# RollerShutterNode_EN.net
KiCad netlist of a schematic drawn in EAGLE
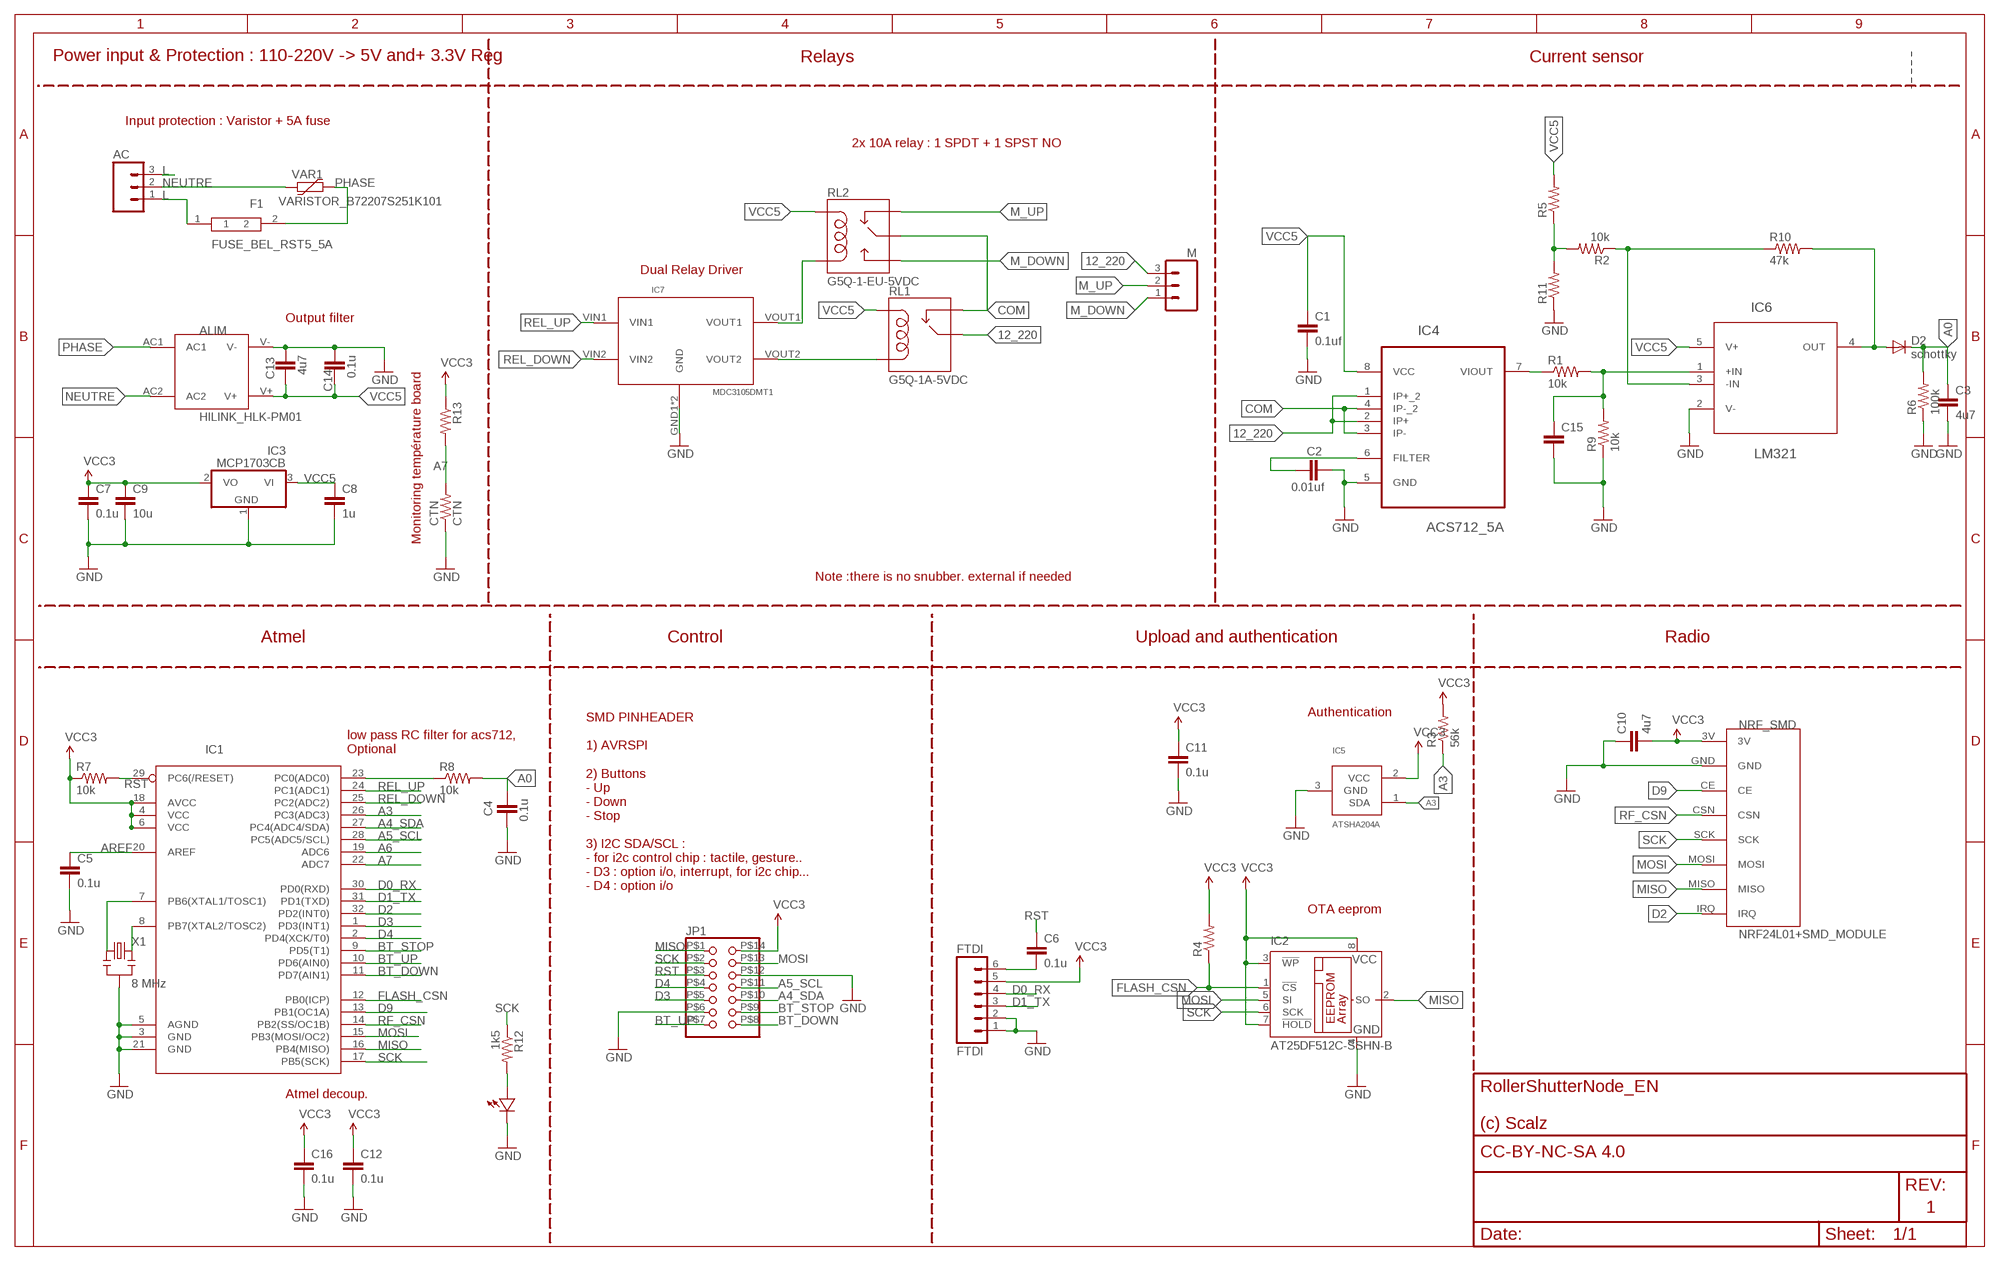
[diagram p0: schematic, sheet 1]

(export (version "E")
  (design (tool "Eeschema 10.0.6"))
  (components
    (comp (ref "AC")
      (value "M03-SCREW-5MM")
      (footprint "eagle-import:SCREWTERMINAL-5MM-3")
      (libsource (lib "eagle-import") (part "M03-SCREW-5MM"))
    )
    (comp (ref "ALIM")
      (value "HILINK_HLK-PM01")
      (footprint "eagle-import:HILINK_HLK-PM01")
      (libsource (lib "eagle-import") (part "HILINK_HLK-PM01"))
    )
    (comp (ref "C1")
      (value "0.1uf")
      (footprint "eagle-import:0805-CAP")
      (libsource (lib "eagle-import") (part "CAP0805-CAP"))
    )
    (comp (ref "C2")
      (value "0.01uf")
      (footprint "eagle-import:0805-CAP")
      (libsource (lib "eagle-import") (part "CAP0805-CAP"))
    )
    (comp (ref "C3")
      (value "4u7")
      (footprint "eagle-import:0805-CAP")
      (libsource (lib "eagle-import") (part "CAP0805-CAP"))
    )
    (comp (ref "C4")
      (value "0.1u")
      (footprint "eagle-import:0805-CAP")
      (libsource (lib "eagle-import") (part "CAP0805-CAP"))
    )
    (comp (ref "C5")
      (value "0.1u")
      (footprint "eagle-import:0805-CAP")
      (libsource (lib "eagle-import") (part "CAP0805-CAP"))
    )
    (comp (ref "C6")
      (value "0.1u")
      (footprint "eagle-import:0805-CAP")
      (libsource (lib "eagle-import") (part "CAP0805-CAP"))
    )
    (comp (ref "C7")
      (value "0.1u")
      (footprint "eagle-import:0805-CAP")
      (libsource (lib "eagle-import") (part "CAP0805-CAP"))
    )
    (comp (ref "C8")
      (value "1u")
      (footprint "eagle-import:0805-CAP")
      (libsource (lib "eagle-import") (part "CAP0805-CAP"))
    )
    (comp (ref "C9")
      (value "10u")
      (footprint "eagle-import:0805-CAP")
      (libsource (lib "eagle-import") (part "CAP0805-CAP"))
    )
    (comp (ref "C10")
      (value "4u7")
      (footprint "eagle-import:0805-CAP")
      (libsource (lib "eagle-import") (part "CAP0805-CAP"))
    )
    (comp (ref "C11")
      (value "0.1u")
      (footprint "eagle-import:0805-CAP")
      (libsource (lib "eagle-import") (part "CAP0805-CAP"))
    )
    (comp (ref "C12")
      (value "0.1u")
      (footprint "eagle-import:0805-CAP")
      (libsource (lib "eagle-import") (part "CAP0805-CAP"))
    )
    (comp (ref "C13")
      (value "4u7")
      (footprint "eagle-import:0805-CAP")
      (libsource (lib "eagle-import") (part "CAP0805-CAP"))
    )
    (comp (ref "C14")
      (value "0.1u")
      (footprint "eagle-import:0805-CAP")
      (libsource (lib "eagle-import") (part "CAP0805-CAP"))
    )
    (comp (ref "C15")
      (value "CAP0805-CAP")
      (footprint "eagle-import:0805-CAP")
      (libsource (lib "eagle-import") (part "CAP0805-CAP"))
    )
    (comp (ref "C16")
      (value "0.1u")
      (footprint "eagle-import:0805-CAP")
      (libsource (lib "eagle-import") (part "CAP0805-CAP"))
    )
    (comp (ref "CTN")
      (value "CTN")
      (footprint "eagle-import:0805-RES")
      (libsource (lib "eagle-import") (part "RESISTOR0805-RES"))
    )
    (comp (ref "D1")
      (value "LED0805")
      (footprint "eagle-import:0805-LED")
      (libsource (lib "eagle-import") (part "LED0805"))
    )
    (comp (ref "D2")
      (value "schottky")
      (footprint "eagle-import:SOD-323")
      (libsource (lib "eagle-import") (part "DIODESOD"))
    )
    (comp (ref "F1")
      (value "FUSE_BEL_RST5_5A")
      (footprint "eagle-import:FUSE_BEL_RST5_5A")
      (libsource (lib "eagle-import") (part "FUSE_BEL_RST5_5A"))
    )
    (comp (ref "FTDI")
      (value "FTDI")
      (footprint "eagle-import:1X06")
      (libsource (lib "eagle-import") (part "M06SIP"))
    )
    (comp (ref "IC1")
      (value "ATMega-328")
      (footprint "eagle-import:TQFP32-08")
      (libsource (lib "eagle-import") (part "ATMEGA168/328TQFP32"))
    )
    (comp (ref "IC2")
      (value "AT25DF512C-SSHN-B")
      (footprint "eagle-import:SO-08")
      (fields (field (name "MF") "MICROCHIP") (field (name "MPN") "25AA080/SN"))
      (libsource (lib "eagle-import") (part "25SNAA080"))
    )
    (comp (ref "IC3")
      (value "MCP1703CB")
      (footprint "eagle-import:SOT23")
      (libsource (lib "eagle-import") (part "MCP1703CB"))
    )
    (comp (ref "IC4")
      (value "ACS712_5A")
      (footprint "eagle-import:SOIC127P600X175-8N")
      (fields (field (name "MPN") "ACS712ELCTR-20A-T"))
      (libsource (lib "eagle-import") (part "ACS712ELCTR-20A-T"))
    )
    (comp (ref "IC5")
      (value "ATSHA204A")
      (footprint "eagle-import:SOT23")
      (libsource (lib "eagle-import") (part "ATSHA204A"))
    )
    (comp (ref "IC6")
      (value "LM321")
      (footprint "eagle-import:SOT95P285X120-5N")
      (fields (field (name "MPN") "LM321MF"))
      (libsource (lib "eagle-import") (part "LM321MF"))
    )
    (comp (ref "IC7")
      (value "MDC3105DMT1")
      (footprint "eagle-import:MDC3105DMT1")
      (libsource (lib "eagle-import") (part "MDC3105DMT1"))
    )
    (comp (ref "JP1")
      (value "PINHD-2X7")
      (footprint "eagle-import:2X07")
      (libsource (lib "eagle-import") (part "PINHD-2X7"))
    )
    (comp (ref "M")
      (value "M03-SCREW-5MM")
      (footprint "eagle-import:SCREWTERMINAL-5MM-3")
      (libsource (lib "eagle-import") (part "M03-SCREW-5MM"))
    )
    (comp (ref "NRF_SMD")
      (value "NRF24L01+SMD_MODULE")
      (footprint "eagle-import:NRF24L01+SMD_MODULE")
      (libsource (lib "eagle-import") (part "NRF24L01+SMD_MODULE"))
    )
    (comp (ref "R1")
      (value "10k")
      (footprint "eagle-import:0805-RES")
      (libsource (lib "eagle-import") (part "RESISTOR0805-RES"))
    )
    (comp (ref "R2")
      (value "10k")
      (footprint "eagle-import:0805-RES")
      (libsource (lib "eagle-import") (part "RESISTOR0805-RES"))
    )
    (comp (ref "R3")
      (value "56k")
      (footprint "eagle-import:0805-RES")
      (libsource (lib "eagle-import") (part "RESISTOR0805-RES"))
    )
    (comp (ref "R4")
      (value "RESISTOR0805-RES")
      (footprint "eagle-import:0805-RES")
      (libsource (lib "eagle-import") (part "RESISTOR0805-RES"))
    )
    (comp (ref "R5")
      (value "RESISTOR0805-RES")
      (footprint "eagle-import:0805-RES")
      (libsource (lib "eagle-import") (part "RESISTOR0805-RES"))
    )
    (comp (ref "R6")
      (value "100k")
      (footprint "eagle-import:0805-RES")
      (libsource (lib "eagle-import") (part "RESISTOR0805-RES"))
    )
    (comp (ref "R7")
      (value "10k")
      (footprint "eagle-import:0805-RES")
      (libsource (lib "eagle-import") (part "RESISTOR0805-RES"))
    )
    (comp (ref "R8")
      (value "10k")
      (footprint "eagle-import:0805-RES")
      (libsource (lib "eagle-import") (part "RESISTOR0805-RES"))
    )
    (comp (ref "R9")
      (value "10k")
      (footprint "eagle-import:0805-RES")
      (libsource (lib "eagle-import") (part "RESISTOR0805-RES"))
    )
    (comp (ref "R10")
      (value "47k")
      (footprint "eagle-import:0805-RES")
      (libsource (lib "eagle-import") (part "RESISTOR0805-RES"))
    )
    (comp (ref "R11")
      (value "RESISTOR0805-RES")
      (footprint "eagle-import:0805-RES")
      (libsource (lib "eagle-import") (part "RESISTOR0805-RES"))
    )
    (comp (ref "R12")
      (value "1k5")
      (footprint "eagle-import:0805-RES")
      (libsource (lib "eagle-import") (part "RESISTOR0805-RES"))
    )
    (comp (ref "R13")
      (value "RESISTOR0805-RES")
      (footprint "eagle-import:0805-RES")
      (libsource (lib "eagle-import") (part "RESISTOR0805-RES"))
    )
    (comp (ref "RL1")
      (value "G5Q-1A-5VDC")
      (footprint "eagle-import:G5Q_SINGLE")
      (libsource (lib "eagle-import") (part "G5Q_SINGLE"))
    )
    (comp (ref "RL2")
      (value "G5Q-1-EU-5VDC")
      (footprint "eagle-import:RELAY-G5Q")
      (libsource (lib "eagle-import") (part "RELAYPTH"))
    )
    (comp (ref "VAR1")
      (value "VARISTOR_B72207S251K101")
      (footprint "eagle-import:VARISTOR_B72207S251K101")
      (libsource (lib "eagle-import") (part "VARISTOR_B72207S251K101"))
    )
    (comp (ref "X1")
      (value "8 MHz")
      (footprint "eagle-import:RESONATOR-SMD")
      (libsource (lib "eagle-import") (part "RESONATORSMD"))
    )
  )
  (nets
    (net (code "1") (name "/A4_SDA") (class "Default")
      (node (ref "IC1") (pin "27") (pinfunction "PC4(ADC4/SDA)_27") (pintype "bidirectional"))
      (node (ref "JP1") (pin "P$10") (pinfunction "10_P$10") (pintype "passive"))
    )
    (net (code "2") (name "/A5_SCL") (class "Default")
      (node (ref "IC1") (pin "28") (pinfunction "PC5(ADC5/SCL)_28") (pintype "bidirectional"))
      (node (ref "JP1") (pin "P$11") (pinfunction "8_P$11") (pintype "passive"))
    )
    (net (code "3") (name "/A6") (class "Default")
      (node (ref "IC1") (pin "19") (pinfunction "ADC6_19") (pintype "bidirectional"))
    )
    (net (code "4") (name "/A7") (class "Default")
      (node (ref "CTN") (pin "2") (pinfunction "2_2") (pintype "passive"))
      (node (ref "IC1") (pin "22") (pinfunction "ADC7_22") (pintype "bidirectional"))
      (node (ref "R13") (pin "2") (pinfunction "2_2") (pintype "passive"))
    )
    (net (code "5") (name "/AREF") (class "Default")
      (node (ref "C5") (pin "1") (pinfunction "1_1") (pintype "passive"))
      (node (ref "IC1") (pin "20") (pinfunction "AREF_20") (pintype "bidirectional"))
    )
    (net (code "6") (name "/BT_DOWN") (class "Default")
      (node (ref "IC1") (pin "11") (pinfunction "PD7(AIN1)_11") (pintype "bidirectional"))
      (node (ref "JP1") (pin "P$8") (pinfunction "14_P$8") (pintype "passive"))
    )
    (net (code "7") (name "/BT_STOP") (class "Default")
      (node (ref "IC1") (pin "9") (pinfunction "PD5(T1)_9") (pintype "bidirectional"))
      (node (ref "JP1") (pin "P$9") (pinfunction "12_P$9") (pintype "passive"))
    )
    (net (code "8") (name "/BT_UP") (class "Default")
      (node (ref "IC1") (pin "10") (pinfunction "PD6(AIN0)_10") (pintype "bidirectional"))
      (node (ref "JP1") (pin "P$7") (pinfunction "13_P$7") (pintype "passive"))
    )
    (net (code "9") (name "/D0_RX") (class "Default")
      (node (ref "FTDI") (pin "4") (pinfunction "4_4") (pintype "passive"))
      (node (ref "IC1") (pin "30") (pinfunction "PD0(RXD)_30") (pintype "bidirectional"))
    )
    (net (code "10") (name "/D1_TX") (class "Default")
      (node (ref "FTDI") (pin "3") (pinfunction "3_3") (pintype "passive"))
      (node (ref "IC1") (pin "31") (pinfunction "PD1(TXD)_31") (pintype "bidirectional"))
    )
    (net (code "11") (name "/D3") (class "Default")
      (node (ref "IC1") (pin "1") (pinfunction "PD3(INT1)_1") (pintype "bidirectional"))
      (node (ref "JP1") (pin "P$5") (pinfunction "9_P$5") (pintype "passive"))
    )
    (net (code "12") (name "/D4") (class "Default")
      (node (ref "IC1") (pin "2") (pinfunction "PD4(XCK/T0)_2") (pintype "bidirectional"))
      (node (ref "JP1") (pin "P$4") (pinfunction "7_P$4") (pintype "passive"))
    )
    (net (code "13") (name "/L") (class "Default")
      (node (ref "AC") (pin "1") (pinfunction "1_1") (pintype "passive"))
      (node (ref "AC") (pin "3") (pinfunction "3_3") (pintype "passive"))
      (node (ref "F1") (pin "1") (pinfunction "1_1") (pintype "bidirectional"))
    )
    (net (code "14") (name "/RST") (class "Default")
      (node (ref "C6") (pin "1") (pinfunction "1_1") (pintype "passive"))
      (node (ref "IC1") (pin "29") (pinfunction "PC6(/RESET)_29") (pintype "bidirectional"))
      (node (ref "JP1") (pin "P$3") (pinfunction "5_P$3") (pintype "passive"))
      (node (ref "R7") (pin "2") (pinfunction "2_2") (pintype "passive"))
    )
    (net (code "15") (name "12_220") (class "Default")
      (node (ref "IC4") (pin "1") (pinfunction "IP+_2_1") (pintype "input"))
      (node (ref "IC4") (pin "2") (pinfunction "IP+_2") (pintype "input"))
      (node (ref "M") (pin "3") (pinfunction "3_3") (pintype "passive"))
      (node (ref "RL1") (pin "2") (pinfunction "MAIN_2") (pintype "bidirectional"))
    )
    (net (code "16") (name "A0") (class "Default")
      (node (ref "C3") (pin "1") (pinfunction "1_1") (pintype "passive"))
      (node (ref "C4") (pin "2") (pinfunction "2_2") (pintype "passive"))
      (node (ref "D2") (pin "1") (pinfunction "C_1") (pintype "passive"))
      (node (ref "R6") (pin "2") (pinfunction "2_2") (pintype "passive"))
      (node (ref "R8") (pin "2") (pinfunction "2_2") (pintype "passive"))
    )
    (net (code "17") (name "A3") (class "Default")
      (node (ref "IC1") (pin "26") (pinfunction "PC3(ADC3)_26") (pintype "bidirectional"))
      (node (ref "IC5") (pin "1") (pinfunction "SDA_1") (pintype "bidirectional"))
      (node (ref "R3") (pin "1") (pinfunction "1_1") (pintype "passive"))
    )
    (net (code "18") (name "COM") (class "Default")
      (node (ref "IC4") (pin "3") (pinfunction "IP-_3") (pintype "input"))
      (node (ref "IC4") (pin "4") (pinfunction "IP-_2_4") (pintype "input"))
      (node (ref "RL1") (pin "3") (pinfunction "NC_3") (pintype "bidirectional"))
      (node (ref "RL2") (pin "2") (pinfunction "MAIN_2") (pintype "bidirectional"))
    )
    (net (code "19") (name "D2") (class "Default")
      (node (ref "IC1") (pin "32") (pinfunction "PD2(INT0)_32") (pintype "bidirectional"))
      (node (ref "NRF_SMD") (pin "IRQ") (pinfunction "IRQ_IRQ") (pintype "bidirectional"))
    )
    (net (code "20") (name "D9") (class "Default")
      (node (ref "IC1") (pin "13") (pinfunction "PB1(OC1A)_13") (pintype "bidirectional"))
      (node (ref "NRF_SMD") (pin "CE") (pinfunction "CE_CE") (pintype "bidirectional"))
    )
    (net (code "21") (name "FLASH_CSN") (class "Default")
      (node (ref "IC1") (pin "12") (pinfunction "PB0(ICP)_12") (pintype "bidirectional"))
      (node (ref "IC2") (pin "1") (pinfunction "~{CS}_1") (pintype "input"))
      (node (ref "R4") (pin "1") (pinfunction "1_1") (pintype "passive"))
    )
    (net (code "22") (name "GND") (class "Default")
      (node (ref "ALIM") (pin "V-") (pinfunction "V-_V-") (pintype "bidirectional"))
      (node (ref "C1") (pin "2") (pinfunction "2_2") (pintype "passive"))
      (node (ref "C10") (pin "1") (pinfunction "1_1") (pintype "passive"))
      (node (ref "C11") (pin "2") (pinfunction "2_2") (pintype "passive"))
      (node (ref "C12") (pin "2") (pinfunction "2_2") (pintype "passive"))
      (node (ref "C13") (pin "2") (pinfunction "2_2") (pintype "passive"))
      (node (ref "C14") (pin "2") (pinfunction "2_2") (pintype "passive"))
      (node (ref "C15") (pin "2") (pinfunction "2_2") (pintype "passive"))
      (node (ref "C16") (pin "2") (pinfunction "2_2") (pintype "passive"))
      (node (ref "C2") (pin "2") (pinfunction "2_2") (pintype "passive"))
      (node (ref "C3") (pin "2") (pinfunction "2_2") (pintype "passive"))
      (node (ref "C4") (pin "1") (pinfunction "1_1") (pintype "passive"))
      (node (ref "C5") (pin "2") (pinfunction "2_2") (pintype "passive"))
      (node (ref "C7") (pin "2") (pinfunction "2_2") (pintype "passive"))
      (node (ref "C8") (pin "2") (pinfunction "2_2") (pintype "passive"))
      (node (ref "C9") (pin "2") (pinfunction "2_2") (pintype "passive"))
      (node (ref "CTN") (pin "1") (pinfunction "1_1") (pintype "passive"))
      (node (ref "D1") (pin "MINUS") (pinfunction "MINUS_MINUS") (pintype "passive"))
      (node (ref "FTDI") (pin "1") (pinfunction "1_1") (pintype "passive"))
      (node (ref "FTDI") (pin "2") (pinfunction "2_2") (pintype "passive"))
      (node (ref "IC1") (pin "21") (pinfunction "GND_21") (pintype "bidirectional"))
      (node (ref "IC1") (pin "3") (pinfunction "GND_3") (pintype "bidirectional"))
      (node (ref "IC1") (pin "5") (pinfunction "AGND_5") (pintype "bidirectional"))
      (node (ref "IC2") (pin "4") (pinfunction "GND_4") (pintype "power_in"))
      (node (ref "IC3") (pin "1") (pinfunction "GND_1") (pintype "passive"))
      (node (ref "IC4") (pin "5") (pinfunction "GND_5") (pintype "passive"))
      (node (ref "IC5") (pin "3") (pinfunction "GND_3") (pintype "bidirectional"))
      (node (ref "IC6") (pin "2") (pinfunction "V-_2") (pintype "power_in"))
      (node (ref "IC7") (pin "GND1") (pinfunction "GND_GND1") (pintype "bidirectional"))
      (node (ref "IC7") (pin "GND2") (pinfunction "GND_GND2") (pintype "bidirectional"))
      (node (ref "JP1") (pin "P$12") (pinfunction "6_P$12") (pintype "passive"))
      (node (ref "JP1") (pin "P$6") (pinfunction "11_P$6") (pintype "passive"))
      (node (ref "NRF_SMD") (pin "GND") (pinfunction "GND_GND") (pintype "bidirectional"))
      (node (ref "R11") (pin "1") (pinfunction "1_1") (pintype "passive"))
      (node (ref "R6") (pin "1") (pinfunction "1_1") (pintype "passive"))
      (node (ref "R9") (pin "1") (pinfunction "1_1") (pintype "passive"))
      (node (ref "X1") (pin "2") (pinfunction "2_2") (pintype "passive"))
    )
    (net (code "23") (name "MISO") (class "Default")
      (node (ref "IC1") (pin "16") (pinfunction "PB4(MISO)_16") (pintype "bidirectional"))
      (node (ref "IC2") (pin "2") (pinfunction "SO_2") (pintype "bidirectional"))
      (node (ref "JP1") (pin "P$1") (pinfunction "1_P$1") (pintype "passive"))
      (node (ref "NRF_SMD") (pin "MISO") (pinfunction "MISO_MISO") (pintype "bidirectional"))
    )
    (net (code "24") (name "MOSI") (class "Default")
      (node (ref "IC1") (pin "15") (pinfunction "PB3(MOSI/OC2)_15") (pintype "bidirectional"))
      (node (ref "IC2") (pin "5") (pinfunction "SI_5") (pintype "input"))
      (node (ref "JP1") (pin "P$13") (pinfunction "4_P$13") (pintype "passive"))
      (node (ref "NRF_SMD") (pin "MOSI") (pinfunction "MOSI_MOSI") (pintype "bidirectional"))
    )
    (net (code "25") (name "M_DOWN") (class "Default")
      (node (ref "M") (pin "1") (pinfunction "1_1") (pintype "passive"))
      (node (ref "RL2") (pin "3") (pinfunction "NO_3") (pintype "bidirectional"))
    )
    (net (code "26") (name "M_UP") (class "Default")
      (node (ref "M") (pin "2") (pinfunction "2_2") (pintype "passive"))
      (node (ref "RL2") (pin "4") (pinfunction "NC_4") (pintype "bidirectional"))
    )
    (net (code "27") (name "NEUTRE") (class "Default")
      (node (ref "AC") (pin "2") (pinfunction "2_2") (pintype "passive"))
      (node (ref "ALIM") (pin "AC2") (pinfunction "AC2_AC2") (pintype "bidirectional"))
      (node (ref "VAR1") (pin "1") (pinfunction "1_1") (pintype "passive"))
    )
    (net (code "28") (name "Net-(C6-Pad2)") (class "Default")
      (node (ref "C6") (pin "2") (pinfunction "2_2") (pintype "passive"))
      (node (ref "FTDI") (pin "6") (pinfunction "6_6") (pintype "passive"))
    )
    (net (code "29") (name "Net-(D1-PadPLUS)") (class "Default")
      (node (ref "D1") (pin "PLUS") (pinfunction "PLUS_PLUS") (pintype "passive"))
      (node (ref "R12") (pin "2") (pinfunction "2_2") (pintype "passive"))
    )
    (net (code "30") (name "Net-(D2-A)") (class "Default")
      (node (ref "D2") (pin "2") (pinfunction "A_2") (pintype "passive"))
      (node (ref "IC6") (pin "4") (pinfunction "OUT_4") (pintype "output"))
      (node (ref "R10") (pin "2") (pinfunction "2_2") (pintype "passive"))
    )
    (net (code "31") (name "Net-(IC1-PB6(XTAL1{slash}TOSC1))") (class "Default")
      (node (ref "IC1") (pin "7") (pinfunction "PB6(XTAL1/TOSC1)_7") (pintype "bidirectional"))
      (node (ref "X1") (pin "1") (pinfunction "1_1") (pintype "passive"))
    )
    (net (code "32") (name "Net-(IC1-PB7(XTAL2{slash}TOSC2))") (class "Default")
      (node (ref "IC1") (pin "8") (pinfunction "PB7(XTAL2/TOSC2)_8") (pintype "bidirectional"))
      (node (ref "X1") (pin "3") (pinfunction "3_3") (pintype "passive"))
    )
    (net (code "33") (name "Net-(IC1-PC0(ADC0))") (class "Default")
      (node (ref "IC1") (pin "23") (pinfunction "PC0(ADC0)_23") (pintype "bidirectional"))
      (node (ref "R8") (pin "1") (pinfunction "1_1") (pintype "passive"))
    )
    (net (code "34") (name "Net-(IC4-FILTER)") (class "Default")
      (node (ref "C2") (pin "1") (pinfunction "1_1") (pintype "passive"))
      (node (ref "IC4") (pin "6") (pinfunction "FILTER_6") (pintype "input"))
    )
    (net (code "35") (name "Net-(IC4-VIOUT)") (class "Default")
      (node (ref "IC4") (pin "7") (pinfunction "VIOUT_7") (pintype "output"))
      (node (ref "R1") (pin "1") (pinfunction "1_1") (pintype "passive"))
    )
    (net (code "36") (name "Net-(IC6-+IN)") (class "Default")
      (node (ref "C15") (pin "1") (pinfunction "1_1") (pintype "passive"))
      (node (ref "IC6") (pin "1") (pinfunction "+IN_1") (pintype "input"))
      (node (ref "R1") (pin "2") (pinfunction "2_2") (pintype "passive"))
      (node (ref "R9") (pin "2") (pinfunction "2_2") (pintype "passive"))
    )
    (net (code "37") (name "Net-(IC6--IN)") (class "Default")
      (node (ref "IC6") (pin "3") (pinfunction "-IN_3") (pintype "input"))
      (node (ref "R10") (pin "1") (pinfunction "1_1") (pintype "passive"))
      (node (ref "R2") (pin "1") (pinfunction "1_1") (pintype "passive"))
    )
    (net (code "38") (name "Net-(R11-Pad2)") (class "Default")
      (node (ref "R11") (pin "2") (pinfunction "2_2") (pintype "passive"))
      (node (ref "R2") (pin "2") (pinfunction "2_2") (pintype "passive"))
      (node (ref "R5") (pin "1") (pinfunction "1_1") (pintype "passive"))
    )
    (net (code "39") (name "Net-(RL1-COIL2)") (class "Default")
      (node (ref "IC7") (pin "VOUT2") (pinfunction "VOUT2_VOUT2") (pintype "bidirectional"))
      (node (ref "RL1") (pin "5") (pinfunction "COIL2_5") (pintype "bidirectional"))
    )
    (net (code "40") (name "Net-(RL2-COIL2)") (class "Default")
      (node (ref "IC7") (pin "VOUT1") (pinfunction "VOUT1_VOUT1") (pintype "bidirectional"))
      (node (ref "RL2") (pin "1") (pinfunction "COIL2_1") (pintype "bidirectional"))
    )
    (net (code "41") (name "PHASE") (class "Default")
      (node (ref "ALIM") (pin "AC1") (pinfunction "AC1_AC1") (pintype "bidirectional"))
      (node (ref "F1") (pin "2") (pinfunction "2_2") (pintype "bidirectional"))
      (node (ref "VAR1") (pin "2") (pinfunction "2_2") (pintype "passive"))
    )
    (net (code "42") (name "REL_DOWN") (class "Default")
      (node (ref "IC1") (pin "25") (pinfunction "PC2(ADC2)_25") (pintype "bidirectional"))
      (node (ref "IC7") (pin "VIN2") (pinfunction "VIN2_VIN2") (pintype "bidirectional"))
    )
    (net (code "43") (name "REL_UP") (class "Default")
      (node (ref "IC1") (pin "24") (pinfunction "PC1(ADC1)_24") (pintype "bidirectional"))
      (node (ref "IC7") (pin "VIN1") (pinfunction "VIN1_VIN1") (pintype "bidirectional"))
    )
    (net (code "44") (name "RF_CSN") (class "Default")
      (node (ref "IC1") (pin "14") (pinfunction "PB2(SS/OC1B)_14") (pintype "bidirectional"))
      (node (ref "NRF_SMD") (pin "CSN") (pinfunction "CSN_CSN") (pintype "bidirectional"))
    )
    (net (code "45") (name "SCK") (class "Default")
      (node (ref "IC1") (pin "17") (pinfunction "PB5(SCK)_17") (pintype "bidirectional"))
      (node (ref "IC2") (pin "6") (pinfunction "SCK_6") (pintype "input"))
      (node (ref "JP1") (pin "P$2") (pinfunction "3_P$2") (pintype "passive"))
      (node (ref "NRF_SMD") (pin "SCK") (pinfunction "SCK_SCK") (pintype "bidirectional"))
      (node (ref "R12") (pin "1") (pinfunction "1_1") (pintype "passive"))
    )
    (net (code "46") (name "VCC3") (class "Default")
      (node (ref "C10") (pin "2") (pinfunction "2_2") (pintype "passive"))
      (node (ref "C11") (pin "1") (pinfunction "1_1") (pintype "passive"))
      (node (ref "C12") (pin "1") (pinfunction "1_1") (pintype "passive"))
      (node (ref "C16") (pin "1") (pinfunction "1_1") (pintype "passive"))
      (node (ref "C7") (pin "1") (pinfunction "1_1") (pintype "passive"))
      (node (ref "C9") (pin "1") (pinfunction "1_1") (pintype "passive"))
      (node (ref "FTDI") (pin "5") (pinfunction "5_5") (pintype "passive"))
      (node (ref "IC1") (pin "18") (pinfunction "AVCC_18") (pintype "bidirectional"))
      (node (ref "IC1") (pin "4") (pinfunction "VCC_4") (pintype "bidirectional"))
      (node (ref "IC1") (pin "6") (pinfunction "VCC_6") (pintype "bidirectional"))
      (node (ref "IC2") (pin "3") (pinfunction "~{WP}_3") (pintype "input"))
      (node (ref "IC2") (pin "7") (pinfunction "~{HOLD}_7") (pintype "input"))
      (node (ref "IC2") (pin "8") (pinfunction "VCC_8") (pintype "power_in"))
      (node (ref "IC3") (pin "2") (pinfunction "VO_2") (pintype "passive"))
      (node (ref "IC5") (pin "2") (pinfunction "VCC_2") (pintype "bidirectional"))
      (node (ref "JP1") (pin "P$14") (pinfunction "2_P$14") (pintype "passive"))
      (node (ref "NRF_SMD") (pin "3V") (pinfunction "3V_3V") (pintype "bidirectional"))
      (node (ref "R13") (pin "1") (pinfunction "1_1") (pintype "passive"))
      (node (ref "R3") (pin "2") (pinfunction "2_2") (pintype "passive"))
      (node (ref "R4") (pin "2") (pinfunction "2_2") (pintype "passive"))
      (node (ref "R7") (pin "1") (pinfunction "1_1") (pintype "passive"))
    )
    (net (code "47") (name "VCC5") (class "Default")
      (node (ref "ALIM") (pin "V+") (pinfunction "V+_V+") (pintype "bidirectional"))
      (node (ref "C1") (pin "1") (pinfunction "1_1") (pintype "passive"))
      (node (ref "C13") (pin "1") (pinfunction "1_1") (pintype "passive"))
      (node (ref "C14") (pin "1") (pinfunction "1_1") (pintype "passive"))
      (node (ref "C8") (pin "1") (pinfunction "1_1") (pintype "passive"))
      (node (ref "IC3") (pin "3") (pinfunction "VI_3") (pintype "input"))
      (node (ref "IC4") (pin "8") (pinfunction "VCC_8") (pintype "power_in"))
      (node (ref "IC6") (pin "5") (pinfunction "V+_5") (pintype "power_in"))
      (node (ref "R5") (pin "2") (pinfunction "2_2") (pintype "passive"))
      (node (ref "RL1") (pin "1") (pinfunction "COIL1_1") (pintype "bidirectional"))
      (node (ref "RL2") (pin "5") (pinfunction "COIL1_5") (pintype "bidirectional"))
    )
  )
)
